# power_eX3.net
KiCad netlist of a schematic drawn in EAGLE
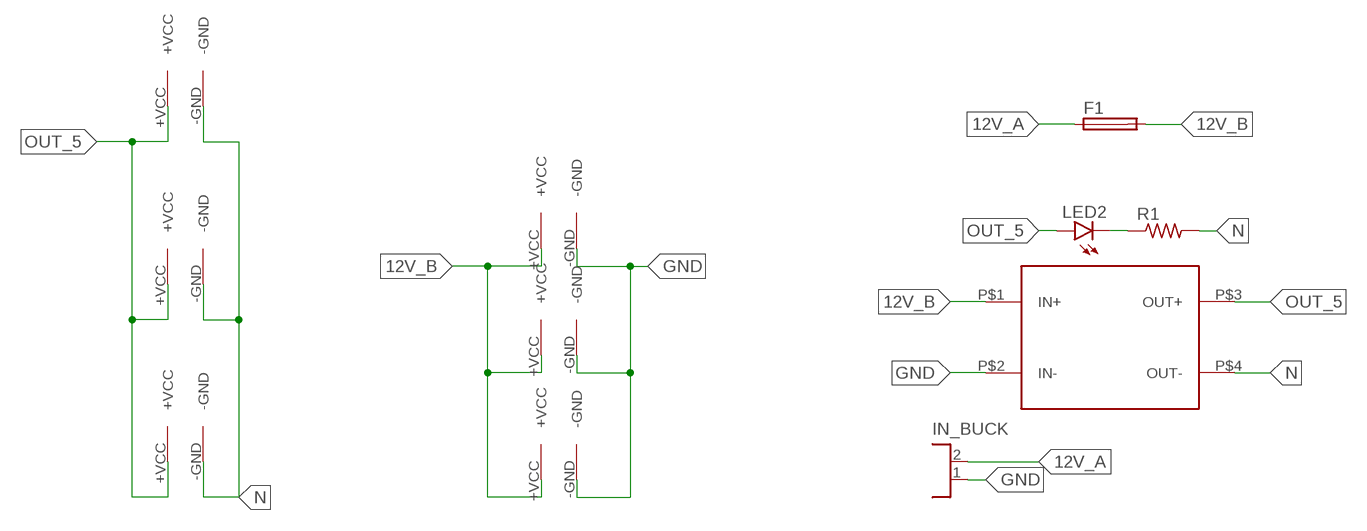
[diagram p0: schematic, sheet 1]

(export (version "E")
  (design (tool "Eeschema 10.0.6"))
  (components
    (comp (ref "F1")
      (value "GSH15")
      (footprint "eagle-import:GSH15")
      (fields (field (name "MPN") "64900001039"))
      (libsource (lib "eagle-import") (part "GSH15"))
    )
    (comp (ref "IN_BUCK")
      (value "2P")
      (footprint "eagle-import:DG55CB-2P-1")
      (libsource (lib "eagle-import") (part "2P"))
    )
    (comp (ref "LED2")
      (value "LED3MM")
      (footprint "eagle-import:LED3MM")
      (libsource (lib "eagle-import") (part "LED3MM"))
    )
    (comp (ref "MM1")
      (value "XT60")
      (footprint "eagle-import:XT60")
      (libsource (lib "eagle-import") (part "XT60"))
    )
    (comp (ref "MM2")
      (value "XT60")
      (footprint "eagle-import:XT60")
      (libsource (lib "eagle-import") (part "XT60"))
    )
    (comp (ref "MM3")
      (value "XT60")
      (footprint "eagle-import:XT60")
      (libsource (lib "eagle-import") (part "XT60"))
    )
    (comp (ref "MM4")
      (value "XT60")
      (footprint "eagle-import:XT60")
      (libsource (lib "eagle-import") (part "XT60"))
    )
    (comp (ref "MM5")
      (value "XT60")
      (footprint "eagle-import:XT60")
      (libsource (lib "eagle-import") (part "XT60"))
    )
    (comp (ref "MM6")
      (value "XT60")
      (footprint "eagle-import:XT60")
      (libsource (lib "eagle-import") (part "XT60"))
    )
    (comp (ref "R1")
      (value "R-US_0207/7")
      (footprint "eagle-import:0207_7")
      (libsource (lib "eagle-import") (part "R-US_0207/7"))
    )
    (comp (ref "U$2")
      (value "LM2595_BUCK_5A_LEDDIP8")
      (footprint "eagle-import:LM2595_BUCK_5A_LED")
      (libsource (lib "eagle-import") (part "LM2595_BUCK_5A_LEDDIP8"))
    )
  )
  (nets
    (net (code "1") (name "12V_A") (class "Default")
      (node (ref "F1") (pin "1") (pinfunction "1_1") (pintype "passive"))
      (node (ref "IN_BUCK") (pin "2") (pinfunction "P$2_2") (pintype "bidirectional"))
    )
    (net (code "2") (name "12V_B") (class "Default")
      (node (ref "F1") (pin "2") (pinfunction "2_2") (pintype "passive"))
      (node (ref "MM4") (pin "+VCC") (pinfunction "+VCC_+VCC") (pintype "bidirectional"))
      (node (ref "MM5") (pin "+VCC") (pinfunction "+VCC_+VCC") (pintype "bidirectional"))
      (node (ref "MM6") (pin "+VCC") (pinfunction "+VCC_+VCC") (pintype "bidirectional"))
      (node (ref "U$2") (pin "P$1") (pinfunction "IN+_P$1") (pintype "bidirectional"))
    )
    (net (code "3") (name "GND") (class "Default")
      (node (ref "IN_BUCK") (pin "1") (pinfunction "P$1_1") (pintype "bidirectional"))
      (node (ref "MM4") (pin "-GND") (pinfunction "-GND_-GND") (pintype "input"))
      (node (ref "MM5") (pin "-GND") (pinfunction "-GND_-GND") (pintype "input"))
      (node (ref "MM6") (pin "-GND") (pinfunction "-GND_-GND") (pintype "input"))
      (node (ref "U$2") (pin "P$2") (pinfunction "IN-_P$2") (pintype "bidirectional"))
    )
    (net (code "4") (name "N") (class "Default")
      (node (ref "MM1") (pin "-GND") (pinfunction "-GND_-GND") (pintype "input"))
      (node (ref "MM2") (pin "-GND") (pinfunction "-GND_-GND") (pintype "input"))
      (node (ref "MM3") (pin "-GND") (pinfunction "-GND_-GND") (pintype "input"))
      (node (ref "R1") (pin "2") (pinfunction "2_2") (pintype "passive"))
      (node (ref "U$2") (pin "P$4") (pinfunction "OUT-_P$4") (pintype "bidirectional"))
    )
    (net (code "5") (name "Net-(LED2-C)") (class "Default")
      (node (ref "LED2") (pin "K") (pinfunction "C_K") (pintype "passive"))
      (node (ref "R1") (pin "1") (pinfunction "1_1") (pintype "passive"))
    )
    (net (code "6") (name "OUT_5") (class "Default")
      (node (ref "LED2") (pin "A") (pinfunction "A_A") (pintype "passive"))
      (node (ref "MM1") (pin "+VCC") (pinfunction "+VCC_+VCC") (pintype "bidirectional"))
      (node (ref "MM2") (pin "+VCC") (pinfunction "+VCC_+VCC") (pintype "bidirectional"))
      (node (ref "MM3") (pin "+VCC") (pinfunction "+VCC_+VCC") (pintype "bidirectional"))
      (node (ref "U$2") (pin "P$3") (pinfunction "OUT+_P$3") (pintype "bidirectional"))
    )
  )
)
